# Noise-Source-Stereo.net
KiCad netlist of a schematic drawn in EAGLE
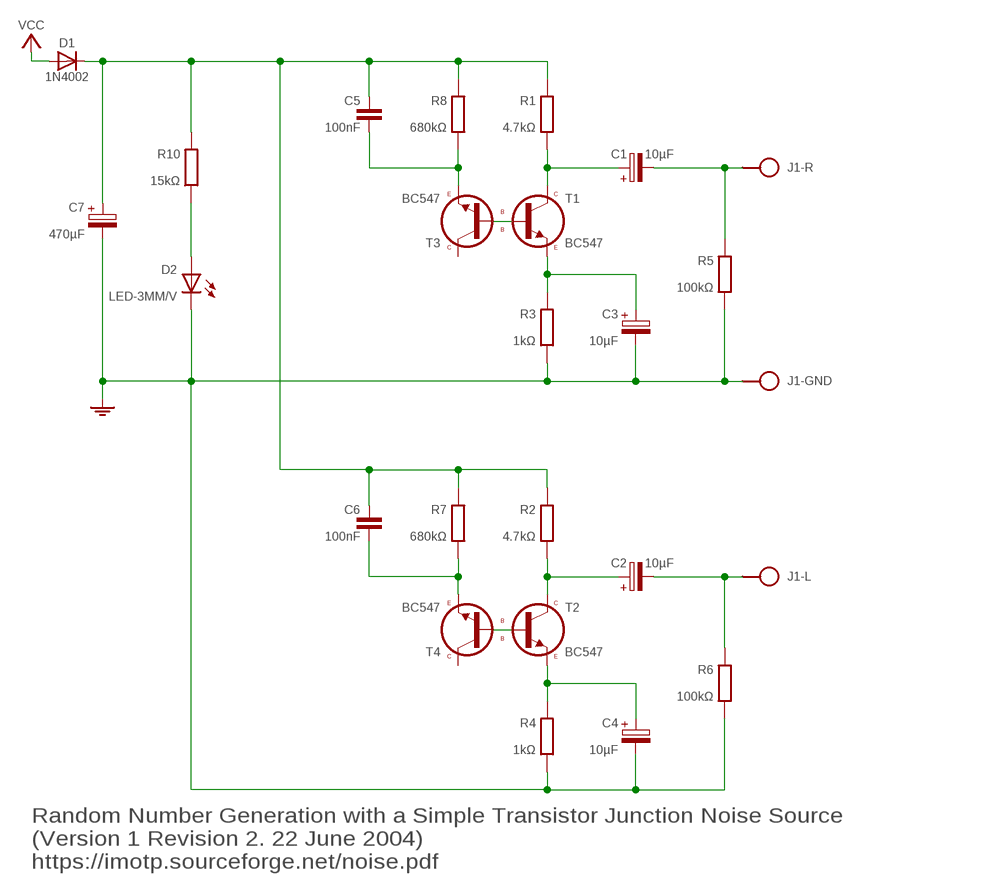
[diagram p0: schematic, sheet 1]

(export (version "E")
  (design (tool "Eeschema 10.0.6"))
  (components
    (comp (ref "C1")
      (value "10µF")
      (footprint "eagle-import:E2,5-5")
      (libsource (lib "eagle-import") (part "CPOL-HE2,5-5"))
    )
    (comp (ref "C2")
      (value "10µF")
      (footprint "eagle-import:E2,5-5")
      (libsource (lib "eagle-import") (part "CPOL-HE2,5-5"))
    )
    (comp (ref "C3")
      (value "10µF")
      (footprint "eagle-import:E2.5-4_V")
      (libsource (lib "eagle-import") (part "CPOLE2,5-4/V"))
    )
    (comp (ref "C4")
      (value "10µF")
      (footprint "eagle-import:E2.5-4_V")
      (libsource (lib "eagle-import") (part "CPOLE2,5-4/V"))
    )
    (comp (ref "C5")
      (value "100nF")
      (footprint "eagle-import:C050-025X075_V")
      (libsource (lib "eagle-import") (part "C050-025X075/V"))
    )
    (comp (ref "C6")
      (value "100nF")
      (footprint "eagle-import:C050-025X075_V")
      (libsource (lib "eagle-import") (part "C050-025X075/V"))
    )
    (comp (ref "C7")
      (value "470µF")
      (footprint "eagle-import:E5-5_V")
      (libsource (lib "eagle-import") (part "CPOLE5-5/V"))
    )
    (comp (ref "D1")
      (value "1N4002")
      (footprint "eagle-import:DO34-7")
      (libsource (lib "eagle-import") (part "DIODE-HDO34-7"))
    )
    (comp (ref "D2")
      (value "LED-3MM/V")
      (footprint "eagle-import:LED_3MM_V")
      (libsource (lib "eagle-import") (part "LED-3MM/V"))
    )
    (comp (ref "GND")
      (value "VCC_GNDL")
      (footprint "eagle-import:SPAD-+")
      (libsource (lib "eagle-import") (part "VCC_GNDL"))
    )
    (comp (ref "J1")
      (value "SAUDIOR-GND-L")
      (footprint "eagle-import:SPAD-R-GND-L")
      (libsource (lib "eagle-import") (part "SAUDIOR-GND-L"))
    )
    (comp (ref "R1")
      (value "4.7kΩ")
      (footprint "eagle-import:0204_10-V")
      (libsource (lib "eagle-import") (part "R0204/10-V"))
    )
    (comp (ref "R2")
      (value "4.7kΩ")
      (footprint "eagle-import:0204_10-V")
      (libsource (lib "eagle-import") (part "R0204/10-V"))
    )
    (comp (ref "R3")
      (value "1kΩ")
      (footprint "eagle-import:0204_10-V")
      (libsource (lib "eagle-import") (part "R0204/10-V"))
    )
    (comp (ref "R4")
      (value "1kΩ")
      (footprint "eagle-import:0204_10")
      (libsource (lib "eagle-import") (part "R0204/10"))
    )
    (comp (ref "R5")
      (value "100kΩ")
      (footprint "eagle-import:0204_10-V")
      (libsource (lib "eagle-import") (part "R0204/10-V"))
    )
    (comp (ref "R6")
      (value "100kΩ")
      (footprint "eagle-import:0204_10-V")
      (libsource (lib "eagle-import") (part "R0204/10-V"))
    )
    (comp (ref "R7")
      (value "680kΩ")
      (footprint "eagle-import:0204_10-V")
      (libsource (lib "eagle-import") (part "R0204/10-V"))
    )
    (comp (ref "R8")
      (value "680kΩ")
      (footprint "eagle-import:0204_10-V")
      (libsource (lib "eagle-import") (part "R0204/10-V"))
    )
    (comp (ref "R10")
      (value "15kΩ")
      (footprint "eagle-import:0204_10-V")
      (libsource (lib "eagle-import") (part "R0204/10-V"))
    )
    (comp (ref "T1")
      (value "BC547")
      (footprint "eagle-import:TO92")
      (libsource (lib "eagle-import") (part "BC547"))
    )
    (comp (ref "T2")
      (value "BC547")
      (footprint "eagle-import:TO92")
      (libsource (lib "eagle-import") (part "BC547"))
    )
    (comp (ref "T3")
      (value "BC547")
      (footprint "eagle-import:TO92")
      (libsource (lib "eagle-import") (part "BC547"))
    )
    (comp (ref "T4")
      (value "BC547")
      (footprint "eagle-import:TO92")
      (libsource (lib "eagle-import") (part "BC547"))
    )
  )
  (nets
    (net (code "1") (name "Net-(D2-C)") (class "Default")
      (node (ref "C3") (pin "-") (pinfunction "-_-") (pintype "passive"))
      (node (ref "C4") (pin "-") (pinfunction "-_-") (pintype "passive"))
      (node (ref "C7") (pin "-") (pinfunction "-_-") (pintype "passive"))
      (node (ref "D2") (pin "K") (pinfunction "C_K") (pintype "passive"))
      (node (ref "GND") (pin "1") (pinfunction "GND_1") (pintype "power_in"))
      (node (ref "J1") (pin "0") (pinfunction "P$1_0") (pintype "passive"))
      (node (ref "R3") (pin "2") (pinfunction "1_2") (pintype "passive"))
      (node (ref "R4") (pin "2") (pinfunction "1_2") (pintype "passive"))
      (node (ref "R5") (pin "2") (pinfunction "1_2") (pintype "passive"))
      (node (ref "R6") (pin "2") (pinfunction "1_2") (pintype "passive"))
    )
    (net (code "2") (name "Net-(GNDA-VCC)") (class "Default")
      (node (ref "D1") (pin "A") (pinfunction "A_A") (pintype "passive"))
      (node (ref "GND") (pin "2") (pinfunction "VCC_2") (pintype "power_in"))
    )
    (net (code "3") (name "Net-(J1B-P$1)") (class "Default")
      (node (ref "C2") (pin "-") (pinfunction "-_-") (pintype "passive"))
      (node (ref "J1") (pin "L") (pinfunction "P$1_L") (pintype "passive"))
      (node (ref "R6") (pin "1") (pinfunction "2_1") (pintype "passive"))
    )
    (net (code "4") (name "Net-(J1C-P$1)") (class "Default")
      (node (ref "C1") (pin "-") (pinfunction "-_-") (pintype "passive"))
      (node (ref "J1") (pin "R") (pinfunction "P$1_R") (pintype "passive"))
      (node (ref "R5") (pin "1") (pinfunction "2_1") (pintype "passive"))
    )
    (net (code "5") (name "Net-(R1-1)") (class "Default")
      (node (ref "C1") (pin "+") (pinfunction "+_+") (pintype "passive"))
      (node (ref "R1") (pin "2") (pinfunction "1_2") (pintype "passive"))
      (node (ref "T1") (pin "1") (pinfunction "C_1") (pintype "passive"))
    )
    (net (code "6") (name "Net-(R1-2)") (class "Default")
      (node (ref "C5") (pin "1") (pinfunction "1_1") (pintype "passive"))
      (node (ref "C6") (pin "1") (pinfunction "1_1") (pintype "passive"))
      (node (ref "C7") (pin "+") (pinfunction "+_+") (pintype "passive"))
      (node (ref "D1") (pin "C") (pinfunction "C_C") (pintype "passive"))
      (node (ref "R1") (pin "1") (pinfunction "2_1") (pintype "passive"))
      (node (ref "R10") (pin "1") (pinfunction "2_1") (pintype "passive"))
      (node (ref "R2") (pin "1") (pinfunction "2_1") (pintype "passive"))
      (node (ref "R7") (pin "1") (pinfunction "2_1") (pintype "passive"))
      (node (ref "R8") (pin "1") (pinfunction "2_1") (pintype "passive"))
    )
    (net (code "7") (name "Net-(R2-1)") (class "Default")
      (node (ref "C2") (pin "+") (pinfunction "+_+") (pintype "passive"))
      (node (ref "R2") (pin "2") (pinfunction "1_2") (pintype "passive"))
      (node (ref "T2") (pin "1") (pinfunction "C_1") (pintype "passive"))
    )
    (net (code "8") (name "Net-(R3-2)") (class "Default")
      (node (ref "C3") (pin "+") (pinfunction "+_+") (pintype "passive"))
      (node (ref "R3") (pin "1") (pinfunction "2_1") (pintype "passive"))
      (node (ref "T1") (pin "3") (pinfunction "E_3") (pintype "passive"))
    )
    (net (code "9") (name "Net-(R4-2)") (class "Default")
      (node (ref "C4") (pin "+") (pinfunction "+_+") (pintype "passive"))
      (node (ref "R4") (pin "1") (pinfunction "2_1") (pintype "passive"))
      (node (ref "T2") (pin "3") (pinfunction "E_3") (pintype "passive"))
    )
    (net (code "10") (name "Net-(R7-1)") (class "Default")
      (node (ref "C6") (pin "2") (pinfunction "2_2") (pintype "passive"))
      (node (ref "R7") (pin "2") (pinfunction "1_2") (pintype "passive"))
      (node (ref "T4") (pin "3") (pinfunction "E_3") (pintype "passive"))
    )
    (net (code "11") (name "Net-(R8-1)") (class "Default")
      (node (ref "C5") (pin "2") (pinfunction "2_2") (pintype "passive"))
      (node (ref "R8") (pin "2") (pinfunction "1_2") (pintype "passive"))
      (node (ref "T3") (pin "3") (pinfunction "E_3") (pintype "passive"))
    )
    (net (code "12") (name "Net-(R10-1)") (class "Default")
      (node (ref "D2") (pin "A") (pinfunction "A_A") (pintype "passive"))
      (node (ref "R10") (pin "2") (pinfunction "1_2") (pintype "passive"))
    )
    (net (code "13") (name "Net-(T1-B)") (class "Default")
      (node (ref "T1") (pin "2") (pinfunction "B_2") (pintype "passive"))
      (node (ref "T3") (pin "2") (pinfunction "B_2") (pintype "passive"))
    )
    (net (code "14") (name "Net-(T2-B)") (class "Default")
      (node (ref "T2") (pin "2") (pinfunction "B_2") (pintype "passive"))
      (node (ref "T4") (pin "2") (pinfunction "B_2") (pintype "passive"))
    )
    (net (code "15") (name "unconnected-(T3-C-Pad1)") (class "Default")
      (node (ref "T3") (pin "1") (pinfunction "C_1") (pintype "passive"))
    )
    (net (code "16") (name "unconnected-(T4-C-Pad1)") (class "Default")
      (node (ref "T4") (pin "1") (pinfunction "C_1") (pintype "passive"))
    )
  )
)
